# DB10011_Toplevel.net
KiCad netlist of a schematic drawn in Altium Designer
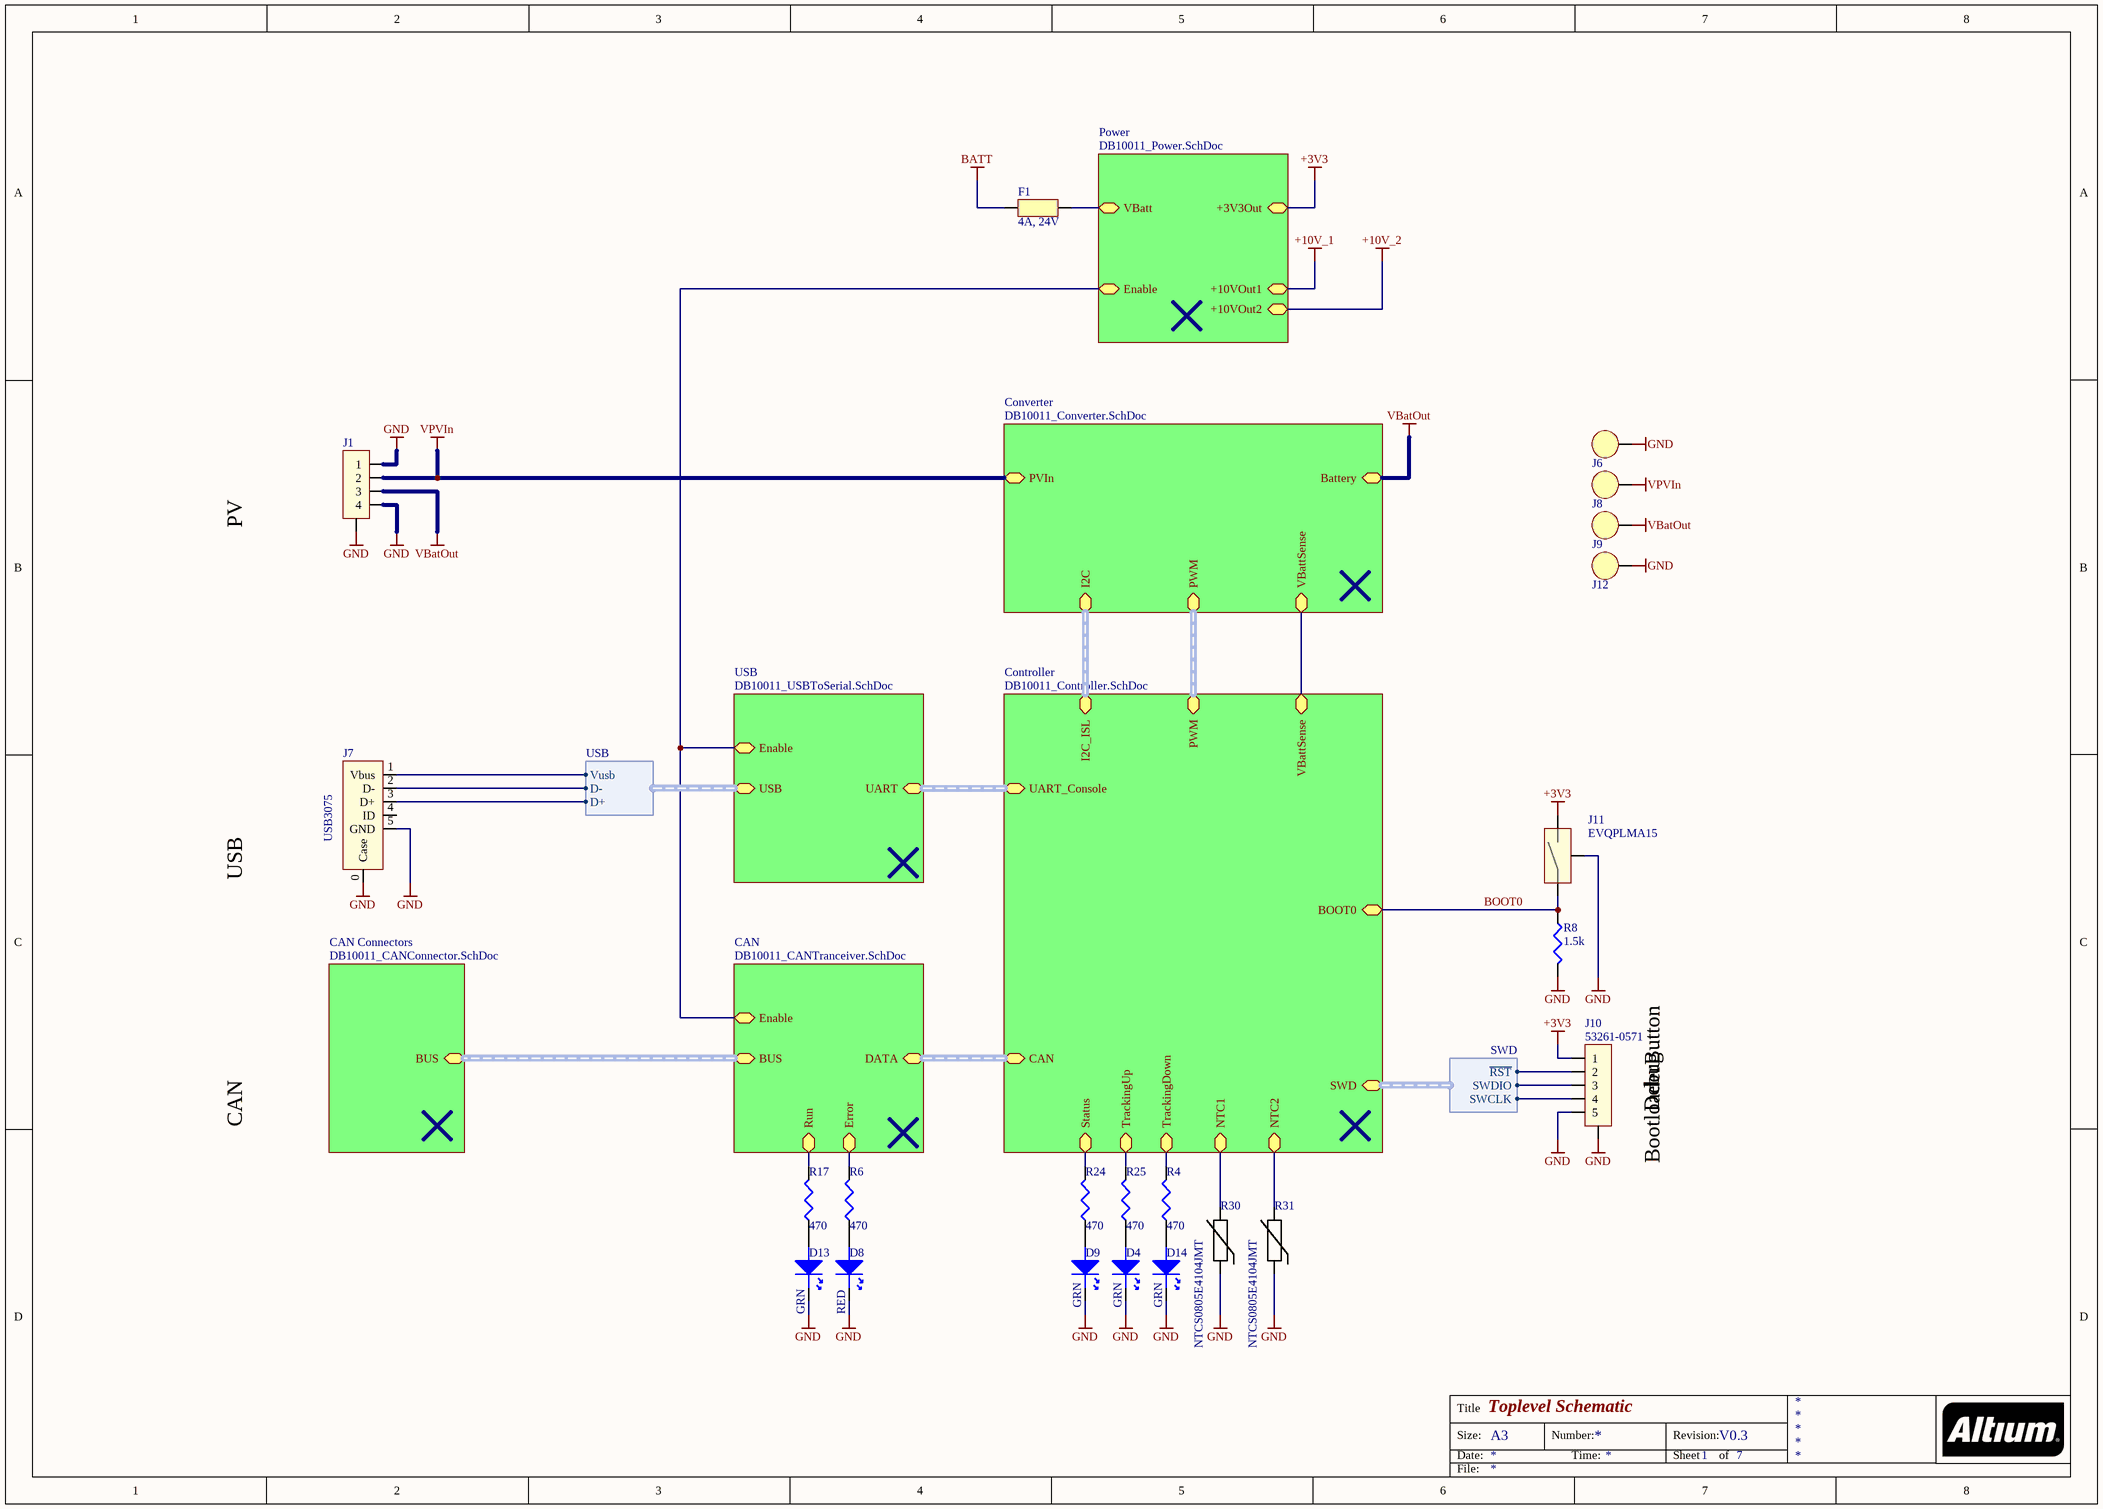
[diagram p0: DB10011_Toplevel.SchDoc]

(export (version "E")
  (design (tool "Eeschema 10.0.6"))
  (components
    (comp (ref "D4")
      (value "GRN")
      (footprint "WL-SMRW_1206 cylindrical_Reverse use")
      (description "LED, Reverse Mount, Cylindrical, Green")
      (libsource (lib "AR_LEDs") (part "156120GS75300"))
    )
    (comp (ref "D8")
      (value "RED")
      (footprint "WL-SMRW_1206 cylindrical_Reverse use")
      (description "LED, Reverse Mount, Cylindrical, Red")
      (libsource (lib "AR_LEDs") (part "156120RS75300"))
    )
    (comp (ref "D9")
      (value "GRN")
      (footprint "WL-SMRW_1206 cylindrical_Reverse use")
      (description "LED, Reverse Mount, Cylindrical, Green")
      (libsource (lib "AR_LEDs") (part "156120GS75300"))
    )
    (comp (ref "D13")
      (value "GRN")
      (footprint "WL-SMRW_1206 cylindrical_Reverse use")
      (description "LED, Reverse Mount, Cylindrical, Green")
      (libsource (lib "AR_LEDs") (part "156120GS75300"))
    )
    (comp (ref "D14")
      (value "GRN")
      (footprint "WL-SMRW_1206 cylindrical_Reverse use")
      (description "LED, Reverse Mount, Cylindrical, Green")
      (libsource (lib "AR_LEDs") (part "156120GS75300"))
    )
    (comp (ref "F1")
      (value "4A, 24V")
      (footprint "F1206")
      (description "Fuse, Slow Blow, 4A, 24V, T:-55°C +125°C")
      (libsource (lib "AR_Misc") (part "MC12CT 004"))
    )
    (comp (ref "J1")
      (value "Header 1x4")
      (footprint "PC 4/ 4-G-7,62")
      (description "Header, Close Horizontal, 1x4, Male, 7.62mm, TH")
      (libsource (lib "AR_Connectors") (part "PC 4/4-G-7,62_1"))
    )
    (comp (ref "J6")
      (value "M3 5mm SMD spacer")
      (footprint "M3_5MM_Spacer")
      (description "M3 5MM Spacer")
      (libsource (lib "AR_Misc") (part "9774050360RWPad"))
    )
    (comp (ref "J7")
      (value "USB3075")
      (footprint "USB3075 - NOSLOT")
      (description "USB 2.0 MICRO B, RCPT, 5POS, SMT")
      (libsource (lib "AR_Connectors") (part "USB3075"))
    )
    (comp (ref "J8")
      (value "M3 5mm SMD spacer")
      (footprint "M3_5MM_Spacer")
      (description "M3 5MM Spacer")
      (libsource (lib "AR_Misc") (part "9774050360RWPad"))
    )
    (comp (ref "J9")
      (value "M3 5mm SMD spacer")
      (footprint "M3_5MM_Spacer")
      (description "M3 5MM Spacer")
      (libsource (lib "AR_Misc") (part "9774050360RWPad"))
    )
    (comp (ref "J10")
      (value "53261-0571")
      (footprint "53261-0571")
      (description "PicoBlade 53261 Series, 5Pin, Right Angle")
      (libsource (lib "AR_Connectors") (part "53261-0571"))
    )
    (comp (ref "J11")
      (value "EVQPLMA15")
      (footprint "EVQPLM")
      (description "SWITCH, TACT, 4.9MM, SMD, 2.6N")
      (libsource (lib "AR_Misc") (part "EVQPLMA15"))
    )
    (comp (ref "J12")
      (value "M3 5mm SMD spacer")
      (footprint "M3_5MM_Spacer")
      (description "M3 5MM Spacer")
      (libsource (lib "AR_Misc") (part "9774050360RWPad"))
    )
    (comp (ref "R4")
      (value "470")
      (footprint "0402")
      (description "Resistor, 470, 1%, 0.0625W, 50V, 100PPM, 0402")
      (libsource (lib "AR_Resistors_SMD") (part "470/0402/0063W/50V"))
    )
    (comp (ref "R6")
      (value "470")
      (footprint "0402")
      (description "Resistor, 470, 1%, 0.0625W, 50V, 100PPM, 0402")
      (libsource (lib "AR_Resistors_SMD") (part "470/0402/0063W/50V"))
    )
    (comp (ref "R8")
      (value "1.5k")
      (footprint "0402")
      (description "Resistor, 1.5k, 0.1%, 0.0625W, 50V, 100PPM, 0402")
      (libsource (lib "AR_Resistors_SMD") (part "1.5k/0402/0063W/50V"))
    )
    (comp (ref "R17")
      (value "470")
      (footprint "0402")
      (description "Resistor, 470, 1%, 0.0625W, 50V, 100PPM, 0402")
      (libsource (lib "AR_Resistors_SMD") (part "470/0402/0063W/50V"))
    )
    (comp (ref "R24")
      (value "470")
      (footprint "0402")
      (description "Resistor, 470, 1%, 0.0625W, 50V, 100PPM, 0402")
      (libsource (lib "AR_Resistors_SMD") (part "470/0402/0063W/50V"))
    )
    (comp (ref "R25")
      (value "470")
      (footprint "0402")
      (description "Resistor, 470, 1%, 0.0625W, 50V, 100PPM, 0402")
      (libsource (lib "AR_Resistors_SMD") (part "470/0402/0063W/50V"))
    )
    (comp (ref "R30")
      (value "NTCS0805E4104JMT")
      (footprint "0805")
      (description "THERMISTOR, NTC, 100K, 5%")
      (libsource (lib "DannyLib") (part "NTCS0805E4104JMT"))
    )
    (comp (ref "R31")
      (value "NTCS0805E4104JMT")
      (footprint "0805")
      (description "THERMISTOR, NTC, 100K, 5%")
      (libsource (lib "DannyLib") (part "NTCS0805E4104JMT"))
    )
  )
  (nets
    (net (code "3") (name "+3V3") (class "Default")
      (node (ref "J10") (pin "1") (pinfunction "1_1") (pintype "passive"))
      (node (ref "J11") (pin "2") (pinfunction "2_2") (pintype "passive"))
    )
    (net (code "6") (name "/BOOT0") (class "Default")
      (node (ref "J11") (pin "1") (pinfunction "1_1") (pintype "passive"))
      (node (ref "R8") (pin "2") (pinfunction "2_2") (pintype "passive"))
    )
    (net (code "9") (name "/D+") (class "Default")
      (node (ref "J7") (pin "3") (pinfunction "D+_3") (pintype "passive"))
    )
    (net (code "10") (name "/D-") (class "Default")
      (node (ref "J7") (pin "2") (pinfunction "D-_2") (pintype "passive"))
    )
    (net (code "12") (name "/Error") (class "Default")
      (node (ref "R6") (pin "2") (pinfunction "2_2") (pintype "passive"))
    )
    (net (code "14") (name "/NTC1") (class "Default")
      (node (ref "R30") (pin "2") (pinfunction "2_2") (pintype "passive"))
    )
    (net (code "15") (name "/NTC2") (class "Default")
      (node (ref "R31") (pin "2") (pinfunction "2_2") (pintype "passive"))
    )
    (net (code "17") (name "/Run") (class "Default")
      (node (ref "R17") (pin "2") (pinfunction "2_2") (pintype "passive"))
    )
    (net (code "18") (name "/SWCLK") (class "Default")
      (node (ref "J10") (pin "4") (pinfunction "4_4") (pintype "passive"))
    )
    (net (code "19") (name "/SWDIO") (class "Default")
      (node (ref "J10") (pin "3") (pinfunction "3_3") (pintype "passive"))
    )
    (net (code "20") (name "/Status") (class "Default")
      (node (ref "R24") (pin "2") (pinfunction "2_2") (pintype "passive"))
    )
    (net (code "21") (name "/TrackingDown") (class "Default")
      (node (ref "R4") (pin "2") (pinfunction "2_2") (pintype "passive"))
    )
    (net (code "22") (name "/TrackingUp") (class "Default")
      (node (ref "R25") (pin "2") (pinfunction "2_2") (pintype "passive"))
    )
    (net (code "24") (name "/VBatt") (class "Default")
      (node (ref "F1") (pin "1") (pinfunction "1_1") (pintype "passive"))
    )
    (net (code "26") (name "/Vusb") (class "Default")
      (node (ref "J7") (pin "1") (pinfunction "Vbus_1") (pintype "passive"))
    )
    (net (code "29") (name "/~{RST}") (class "Default")
      (node (ref "J10") (pin "2") (pinfunction "2_2") (pintype "passive"))
    )
    (net (code "30") (name "BATT") (class "Default")
      (node (ref "F1") (pin "2") (pinfunction "2_2") (pintype "passive"))
    )
    (net (code "31") (name "GND") (class "Default")
      (node (ref "D13") (pin "1") (pinfunction "K_1") (pintype "passive"))
      (node (ref "D14") (pin "1") (pinfunction "K_1") (pintype "passive"))
      (node (ref "D4") (pin "1") (pinfunction "K_1") (pintype "passive"))
      (node (ref "D8") (pin "1") (pinfunction "K_1") (pintype "passive"))
      (node (ref "D9") (pin "1") (pinfunction "K_1") (pintype "passive"))
      (node (ref "J1") (pin "0") (pinfunction "0_0") (pintype "passive"))
      (node (ref "J1") (pin "1") (pinfunction "1_1") (pintype "passive"))
      (node (ref "J1") (pin "4") (pinfunction "4_4") (pintype "passive"))
      (node (ref "J10") (pin "0") (pinfunction "SHLD_0") (pintype "passive"))
      (node (ref "J10") (pin "5") (pinfunction "5_5") (pintype "passive"))
      (node (ref "J11") (pin "0") (pinfunction "GND_0") (pintype "passive"))
      (node (ref "J12") (pin "0") (pinfunction "0_0") (pintype "passive"))
      (node (ref "J6") (pin "0") (pinfunction "0_0") (pintype "passive"))
      (node (ref "J7") (pin "0") (pinfunction "Case_0") (pintype "passive"))
      (node (ref "J7") (pin "5") (pinfunction "GND_5") (pintype "passive"))
      (node (ref "R30") (pin "1") (pinfunction "1_1") (pintype "passive"))
      (node (ref "R31") (pin "1") (pinfunction "1_1") (pintype "passive"))
      (node (ref "R8") (pin "1") (pinfunction "1_1") (pintype "passive"))
    )
    (net (code "32") (name "Net-(D4-A)") (class "Default")
      (node (ref "D4") (pin "2") (pinfunction "A_2") (pintype "passive"))
      (node (ref "R25") (pin "1") (pinfunction "1_1") (pintype "passive"))
    )
    (net (code "33") (name "Net-(D8-A)") (class "Default")
      (node (ref "D8") (pin "2") (pinfunction "A_2") (pintype "passive"))
      (node (ref "R6") (pin "1") (pinfunction "1_1") (pintype "passive"))
    )
    (net (code "34") (name "Net-(D9-A)") (class "Default")
      (node (ref "D9") (pin "2") (pinfunction "A_2") (pintype "passive"))
      (node (ref "R24") (pin "1") (pinfunction "1_1") (pintype "passive"))
    )
    (net (code "35") (name "Net-(D13-A)") (class "Default")
      (node (ref "D13") (pin "2") (pinfunction "A_2") (pintype "passive"))
      (node (ref "R17") (pin "1") (pinfunction "1_1") (pintype "passive"))
    )
    (net (code "36") (name "Net-(D14-A)") (class "Default")
      (node (ref "D14") (pin "2") (pinfunction "A_2") (pintype "passive"))
      (node (ref "R4") (pin "1") (pinfunction "1_1") (pintype "passive"))
    )
    (net (code "37") (name "VBatOut") (class "Default")
      (node (ref "J1") (pin "3") (pinfunction "3_3") (pintype "passive"))
      (node (ref "J9") (pin "0") (pinfunction "0_0") (pintype "passive"))
    )
    (net (code "38") (name "VPVIn") (class "Default")
      (node (ref "J1") (pin "2") (pinfunction "2_2") (pintype "passive"))
      (node (ref "J8") (pin "0") (pinfunction "0_0") (pintype "passive"))
    )
    (net (code "39") (name "unconnected-(J7-ID-Pad4)") (class "Default")
      (node (ref "J7") (pin "4") (pinfunction "ID_4") (pintype "passive"))
    )
  )
)
